# Camera.net
KiCad netlist of a schematic drawn in Altium Designer
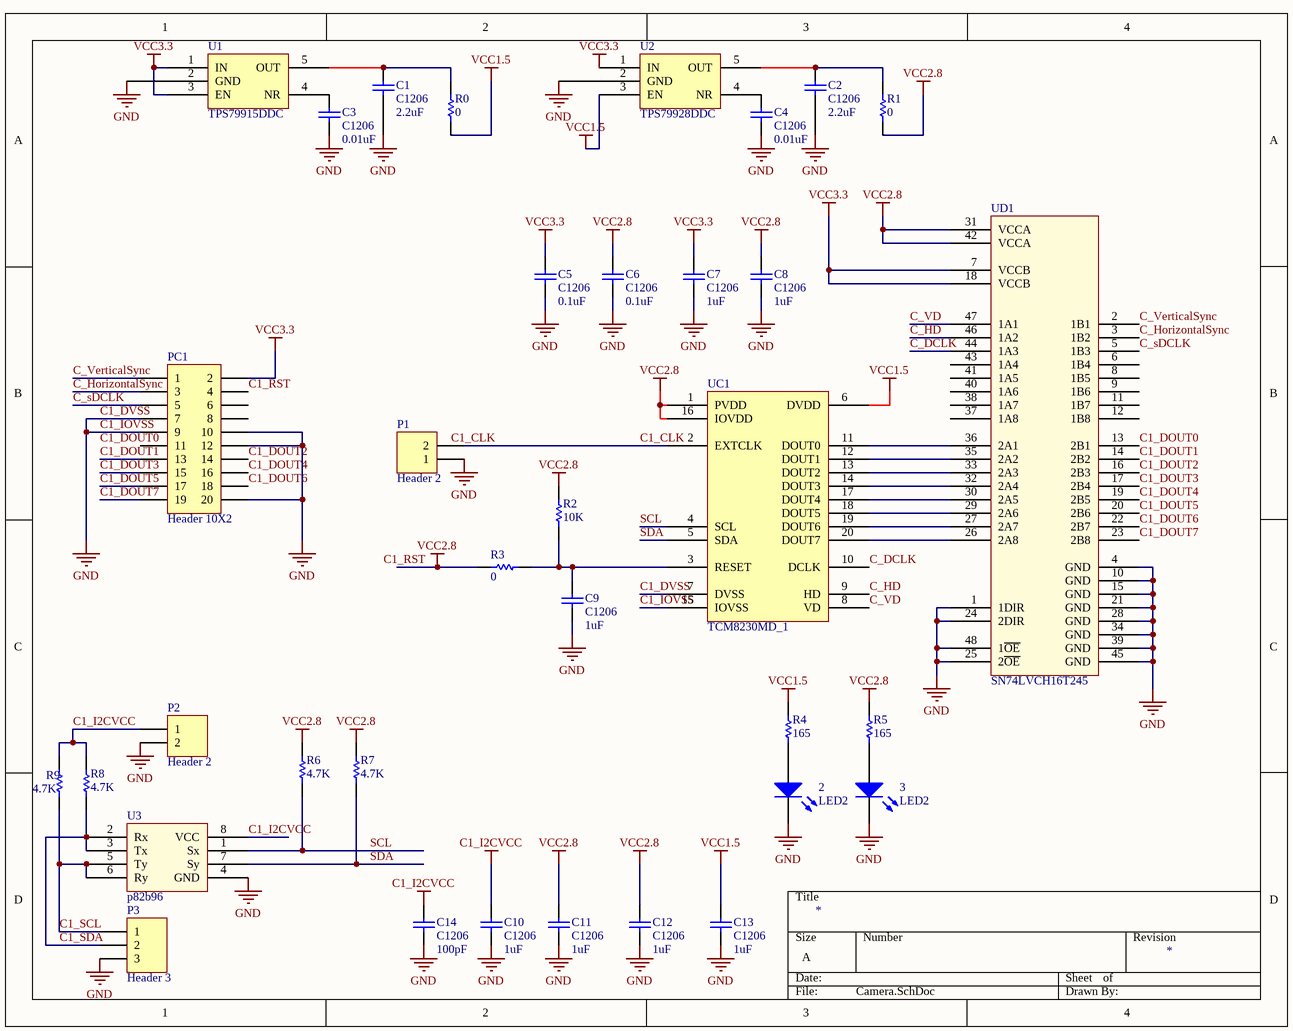
[diagram p0: Camera.SchDoc]

(export (version "E")
  (design (tool "Eeschema 10.0.6"))
  (components
    (comp (ref "2")
      (value "LED2")
      (footprint "DIODE1608")
      (description "Typical RED, GREEN, YELLOW, AMBER GaAs LED")
      (fields (field (name "PUBLISHER") "Altium Limited"))
      (libsource (lib "Miscellaneous Devices") (part "LED2"))
    )
    (comp (ref "3")
      (value "LED2")
      (footprint "DIODE1608")
      (description "Typical RED, GREEN, YELLOW, AMBER GaAs LED")
      (fields (field (name "PUBLISHER") "Altium Limited"))
      (libsource (lib "Miscellaneous Devices") (part "LED2"))
    )
    (comp (ref "C1")
      (value "C1206")
      (footprint "1206")
      (description "Ceramic Chip Capacitor - Standard")
      (fields (field (name "ALTIUM_VALUE") "2.2uF") (field (name "PUBLISHER") "Altium Limited"))
      (libsource (lib "KEMET Chip Capacitor") (part "C1206"))
    )
    (comp (ref "C2")
      (value "C1206")
      (footprint "1206")
      (description "Ceramic Chip Capacitor - Standard")
      (fields (field (name "ALTIUM_VALUE") "2.2uF") (field (name "PUBLISHER") "Altium Limited"))
      (libsource (lib "KEMET Chip Capacitor") (part "C1206"))
    )
    (comp (ref "C3")
      (value "C1206")
      (footprint "1206")
      (description "Ceramic Chip Capacitor - Standard")
      (fields (field (name "ALTIUM_VALUE") "0.01uF") (field (name "PUBLISHER") "Altium Limited"))
      (libsource (lib "KEMET Chip Capacitor") (part "C1206"))
    )
    (comp (ref "C4")
      (value "C1206")
      (footprint "1206")
      (description "Ceramic Chip Capacitor - Standard")
      (fields (field (name "ALTIUM_VALUE") "0.01uF") (field (name "PUBLISHER") "Altium Limited"))
      (libsource (lib "KEMET Chip Capacitor") (part "C1206"))
    )
    (comp (ref "C5")
      (value "C1206")
      (footprint "1206")
      (description "Ceramic Chip Capacitor - Standard")
      (fields (field (name "ALTIUM_VALUE") "0.1uF") (field (name "PUBLISHER") "Altium Limited"))
      (libsource (lib "KEMET Chip Capacitor") (part "C1206"))
    )
    (comp (ref "C6")
      (value "C1206")
      (footprint "1206")
      (description "Ceramic Chip Capacitor - Standard")
      (fields (field (name "ALTIUM_VALUE") "0.1uF") (field (name "PUBLISHER") "Altium Limited"))
      (libsource (lib "KEMET Chip Capacitor") (part "C1206"))
    )
    (comp (ref "C7")
      (value "C1206")
      (footprint "1206")
      (description "Ceramic Chip Capacitor - Standard")
      (fields (field (name "ALTIUM_VALUE") "1uF") (field (name "PUBLISHER") "Altium Limited"))
      (libsource (lib "KEMET Chip Capacitor") (part "C1206"))
    )
    (comp (ref "C8")
      (value "C1206")
      (footprint "1206")
      (description "Ceramic Chip Capacitor - Standard")
      (fields (field (name "ALTIUM_VALUE") "1uF") (field (name "PUBLISHER") "Altium Limited"))
      (libsource (lib "KEMET Chip Capacitor") (part "C1206"))
    )
    (comp (ref "C9")
      (value "C1206")
      (footprint "1206")
      (description "Ceramic Chip Capacitor - Standard")
      (fields (field (name "ALTIUM_VALUE") "1uF") (field (name "PUBLISHER") "Altium Limited"))
      (libsource (lib "KEMET Chip Capacitor") (part "C1206"))
    )
    (comp (ref "C10")
      (value "C1206")
      (footprint "1206")
      (description "Ceramic Chip Capacitor - Standard")
      (fields (field (name "ALTIUM_VALUE") "1uF") (field (name "PUBLISHER") "Altium Limited"))
      (libsource (lib "KEMET Chip Capacitor") (part "C1206"))
    )
    (comp (ref "C11")
      (value "C1206")
      (footprint "1206")
      (description "Ceramic Chip Capacitor - Standard")
      (fields (field (name "ALTIUM_VALUE") "1uF") (field (name "PUBLISHER") "Altium Limited"))
      (libsource (lib "KEMET Chip Capacitor") (part "C1206"))
    )
    (comp (ref "C12")
      (value "C1206")
      (footprint "1206")
      (description "Ceramic Chip Capacitor - Standard")
      (fields (field (name "ALTIUM_VALUE") "1uF") (field (name "PUBLISHER") "Altium Limited"))
      (libsource (lib "KEMET Chip Capacitor") (part "C1206"))
    )
    (comp (ref "C13")
      (value "C1206")
      (footprint "1206")
      (description "Ceramic Chip Capacitor - Standard")
      (fields (field (name "ALTIUM_VALUE") "1uF") (field (name "PUBLISHER") "Altium Limited"))
      (libsource (lib "KEMET Chip Capacitor") (part "C1206"))
    )
    (comp (ref "C14")
      (value "C1206")
      (footprint "1206")
      (description "Ceramic Chip Capacitor - Standard")
      (fields (field (name "ALTIUM_VALUE") "100pF") (field (name "PUBLISHER") "Altium Limited"))
      (libsource (lib "KEMET Chip Capacitor") (part "C1206"))
    )
    (comp (ref "P1")
      (value "Header 2")
      (footprint "HDR1X2")
      (description "Header, 2-Pin")
      (fields (field (name "PUBLISHER") "Altium Limited"))
      (libsource (lib "") (part "Header 2_1"))
    )
    (comp (ref "P2")
      (value "Header 2")
      (footprint "HDR1X2")
      (description "Header, 2-Pin")
      (fields (field (name "PUBLISHER") "Altium Limited"))
      (libsource (lib "Miscellaneous Connectors") (part "Header 2"))
    )
    (comp (ref "P3")
      (value "Header 3")
      (footprint "HDR1X3")
      (description "Header, 3-Pin")
      (fields (field (name "PUBLISHER") "Altium Limited"))
      (libsource (lib "Miscellaneous Connectors") (part "Header 3"))
    )
    (comp (ref "PC1")
      (value "Header 10X2")
      (footprint "HDR2X10")
      (description "Header, 10-Pin, Dual row")
      (fields (field (name "PUBLISHER") "Altium Limited"))
      (libsource (lib "Miscellaneous Connectors") (part "Header 10X2"))
    )
    (comp (ref "R0")
      (value "0")
      (footprint "8-1206")
      (description "Thick Film Chip Resistor, 1 Ohm to 10M Ohm Range, 5% Tolerance, 1206 Size, 0.25 W")
      (fields (field (name "PUBLISHER") "Altium Limited"))
      (libsource (lib "Panasonic Resistor") (part "ERJ8GE"))
    )
    (comp (ref "R1")
      (value "0")
      (footprint "8-1206")
      (description "Thick Film Chip Resistor, 1 Ohm to 10M Ohm Range, 5% Tolerance, 1206 Size, 0.25 W")
      (fields (field (name "PUBLISHER") "Altium Limited"))
      (libsource (lib "Panasonic Resistor") (part "ERJ8GE"))
    )
    (comp (ref "R2")
      (value "10K")
      (footprint "8-1206")
      (description "Thick Film Chip Resistor, 1 Ohm to 10M Ohm Range, 5% Tolerance, 1206 Size, 0.25 W")
      (fields (field (name "PUBLISHER") "Altium Limited"))
      (libsource (lib "Panasonic Resistor") (part "ERJ8GE"))
    )
    (comp (ref "R3")
      (value "0")
      (footprint "8-1206")
      (description "Thick Film Chip Resistor, 1 Ohm to 10M Ohm Range, 5% Tolerance, 1206 Size, 0.25 W")
      (fields (field (name "PUBLISHER") "Altium Limited"))
      (libsource (lib "Panasonic Resistor") (part "ERJ8GE"))
    )
    (comp (ref "R4")
      (value "165")
      (footprint "8-1206")
      (description "Thick Film Chip Resistor, 1 Ohm to 10M Ohm Range, 5% Tolerance, 1206 Size, 0.25 W")
      (fields (field (name "PUBLISHER") "Altium Limited"))
      (libsource (lib "Panasonic Resistor") (part "ERJ8GE"))
    )
    (comp (ref "R5")
      (value "165")
      (footprint "8-1206")
      (description "Thick Film Chip Resistor, 1 Ohm to 10M Ohm Range, 5% Tolerance, 1206 Size, 0.25 W")
      (fields (field (name "PUBLISHER") "Altium Limited"))
      (libsource (lib "Panasonic Resistor") (part "ERJ8GE"))
    )
    (comp (ref "R6")
      (value "4.7K")
      (footprint "8-1206")
      (description "Thick Film Chip Resistor, 1 Ohm to 10M Ohm Range, 5% Tolerance, 1206 Size, 0.25 W")
      (fields (field (name "PUBLISHER") "Altium Limited"))
      (libsource (lib "Panasonic Resistor") (part "ERJ8GE"))
    )
    (comp (ref "R7")
      (value "4.7K")
      (footprint "8-1206")
      (description "Thick Film Chip Resistor, 1 Ohm to 10M Ohm Range, 5% Tolerance, 1206 Size, 0.25 W")
      (fields (field (name "PUBLISHER") "Altium Limited"))
      (libsource (lib "Panasonic Resistor") (part "ERJ8GE"))
    )
    (comp (ref "R8")
      (value "4.7K")
      (footprint "8-1206")
      (description "Thick Film Chip Resistor, 1 Ohm to 10M Ohm Range, 5% Tolerance, 1206 Size, 0.25 W")
      (fields (field (name "PUBLISHER") "Altium Limited"))
      (libsource (lib "Panasonic Resistor") (part "ERJ8GE"))
    )
    (comp (ref "R9")
      (value "4.7K")
      (footprint "8-1206")
      (description "Thick Film Chip Resistor, 1 Ohm to 10M Ohm Range, 5% Tolerance, 1206 Size, 0.25 W")
      (fields (field (name "PUBLISHER") "Altium Limited"))
      (libsource (lib "Panasonic Resistor") (part "ERJ8GE"))
    )
    (comp (ref "U1")
      (value "TPS79915DDC")
      (footprint "TSOT23-5")
      (description "200mA, Low Quiescent Current, Ultra-Low Noise, High PSRR  Low Dropout Linear Regulator")
      (libsource (lib "Capstone_Lib") (part "TPS799xxDDC"))
    )
    (comp (ref "U2")
      (value "TPS79928DDC")
      (footprint "TSOT23-5")
      (description "200mA, Low Quiescent Current, Ultra-Low Noise, High PSRR  Low Dropout Linear Regulator")
      (libsource (lib "Capstone_Lib") (part "TPS799xxDDC"))
    )
    (comp (ref "U3") (value "p82b96") (footprint "DIP-8") (libsource (lib "p82b96") (part "p82b96")))
    (comp (ref "UC1")
      (value "TCM8230MD_1")
      (footprint "TCM8230MD")
      (description "VGA CAMERA MODULE 640x480")
      (libsource (lib "daughterboard") (part "TCM8230MD_1"))
    )
    (comp (ref "UD1")
      (value "SN74LVCH16T245")
      (footprint "SN74LVCH16T245")
      (description "16-bit bus transceiver with voltage regulation.")
      (libsource (lib "daughterboard") (part "SN74LVCH16T245"))
    )
  )
  (nets
    (net (code "1") (name "/C1_CLK") (class "Default")
      (node (ref "P1") (pin "2") (pinfunction "2_2") (pintype "passive"))
      (node (ref "UC1") (pin "2") (pinfunction "EXTCLK_2") (pintype "passive"))
    )
    (net (code "2") (name "/C1_DOUT0") (class "Default")
      (node (ref "UD1") (pin "13") (pinfunction "2B1_13") (pintype "passive"))
    )
    (net (code "3") (name "/C1_DOUT1") (class "Default")
      (node (ref "PC1") (pin "13") (pinfunction "13_13") (pintype "passive"))
      (node (ref "UD1") (pin "14") (pinfunction "2B2_14") (pintype "passive"))
    )
    (net (code "4") (name "/C1_DOUT2") (class "Default")
      (node (ref "PC1") (pin "14") (pinfunction "14_14") (pintype "passive"))
      (node (ref "UD1") (pin "16") (pinfunction "2B3_16") (pintype "passive"))
    )
    (net (code "5") (name "/C1_DOUT3") (class "Default")
      (node (ref "PC1") (pin "15") (pinfunction "15_15") (pintype "passive"))
      (node (ref "UD1") (pin "17") (pinfunction "2B4_17") (pintype "passive"))
    )
    (net (code "6") (name "/C1_DOUT4") (class "Default")
      (node (ref "PC1") (pin "16") (pinfunction "16_16") (pintype "passive"))
      (node (ref "UD1") (pin "19") (pinfunction "2B5_19") (pintype "passive"))
    )
    (net (code "7") (name "/C1_DOUT5") (class "Default")
      (node (ref "PC1") (pin "17") (pinfunction "17_17") (pintype "passive"))
      (node (ref "UD1") (pin "20") (pinfunction "2B6_20") (pintype "passive"))
    )
    (net (code "8") (name "/C1_DOUT6") (class "Default")
      (node (ref "PC1") (pin "18") (pinfunction "18_18") (pintype "passive"))
      (node (ref "UD1") (pin "22") (pinfunction "2B7_22") (pintype "passive"))
    )
    (net (code "9") (name "/C1_DOUT7") (class "Default")
      (node (ref "PC1") (pin "19") (pinfunction "19_19") (pintype "passive"))
      (node (ref "UD1") (pin "23") (pinfunction "2B8_23") (pintype "passive"))
    )
    (net (code "10") (name "/C1_RST") (class "Default")
      (node (ref "PC1") (pin "4") (pinfunction "4_4") (pintype "passive"))
    )
    (net (code "11") (name "/C1_SCL") (class "Default")
      (node (ref "P3") (pin "1") (pinfunction "1_1") (pintype "passive"))
      (node (ref "R9") (pin "1") (pinfunction "1_1") (pintype "passive"))
      (node (ref "U3") (pin "5") (pinfunction "Ty_5") (pintype "passive"))
      (node (ref "U3") (pin "6") (pinfunction "Ry_6") (pintype "passive"))
    )
    (net (code "12") (name "/C1_SDA") (class "Default")
      (node (ref "P3") (pin "2") (pinfunction "2_2") (pintype "passive"))
      (node (ref "R8") (pin "1") (pinfunction "1_1") (pintype "passive"))
      (node (ref "U3") (pin "2") (pinfunction "Rx_2") (pintype "passive"))
      (node (ref "U3") (pin "3") (pinfunction "Tx_3") (pintype "passive"))
    )
    (net (code "13") (name "/C_DCLK") (class "Default")
      (node (ref "UC1") (pin "10") (pinfunction "DCLK_10") (pintype "passive"))
      (node (ref "UD1") (pin "44") (pinfunction "1A3_44") (pintype "passive"))
    )
    (net (code "14") (name "/C_HD") (class "Default")
      (node (ref "UC1") (pin "9") (pinfunction "HD_9") (pintype "passive"))
      (node (ref "UD1") (pin "46") (pinfunction "1A2_46") (pintype "passive"))
    )
    (net (code "15") (name "/C_HorizontalSync") (class "Default")
      (node (ref "PC1") (pin "3") (pinfunction "3_3") (pintype "passive"))
      (node (ref "UD1") (pin "3") (pinfunction "1B2_3") (pintype "passive"))
    )
    (net (code "16") (name "/C_VD") (class "Default")
      (node (ref "UC1") (pin "8") (pinfunction "VD_8") (pintype "passive"))
      (node (ref "UD1") (pin "47") (pinfunction "1A1_47") (pintype "passive"))
    )
    (net (code "17") (name "/C_VerticalSync") (class "Default")
      (node (ref "PC1") (pin "1") (pinfunction "1_1") (pintype "passive"))
      (node (ref "UD1") (pin "2") (pinfunction "1B1_2") (pintype "passive"))
    )
    (net (code "18") (name "/C_sDCLK") (class "Default")
      (node (ref "PC1") (pin "5") (pinfunction "5_5") (pintype "passive"))
      (node (ref "UD1") (pin "5") (pinfunction "1B3_5") (pintype "passive"))
    )
    (net (code "19") (name "/SCL") (class "Default")
      (node (ref "R6") (pin "1") (pinfunction "1_1") (pintype "passive"))
      (node (ref "U3") (pin "1") (pinfunction "Sx_1") (pintype "passive"))
      (node (ref "UC1") (pin "4") (pinfunction "SCL_4") (pintype "passive"))
    )
    (net (code "20") (name "/SDA") (class "Default")
      (node (ref "R7") (pin "1") (pinfunction "1_1") (pintype "passive"))
      (node (ref "U3") (pin "7") (pinfunction "Sy_7") (pintype "passive"))
      (node (ref "UC1") (pin "5") (pinfunction "SDA_5") (pintype "passive"))
    )
    (net (code "21") (name "C1_I2CVCC") (class "Default")
      (node (ref "C10") (pin "2") (pinfunction "2_2") (pintype "passive"))
      (node (ref "C14") (pin "2") (pinfunction "2_2") (pintype "passive"))
      (node (ref "P2") (pin "1") (pinfunction "1_1") (pintype "passive"))
      (node (ref "R8") (pin "2") (pinfunction "2_2") (pintype "passive"))
      (node (ref "R9") (pin "2") (pinfunction "2_2") (pintype "passive"))
      (node (ref "U3") (pin "8") (pinfunction "VCC_8") (pintype "passive"))
    )
    (net (code "22") (name "GND") (class "Default")
      (node (ref "2") (pin "2") (pinfunction "K_2") (pintype "passive"))
      (node (ref "3") (pin "2") (pinfunction "K_2") (pintype "passive"))
      (node (ref "C1") (pin "1") (pinfunction "1_1") (pintype "passive"))
      (node (ref "C10") (pin "1") (pinfunction "1_1") (pintype "passive"))
      (node (ref "C11") (pin "1") (pinfunction "1_1") (pintype "passive"))
      (node (ref "C12") (pin "1") (pinfunction "1_1") (pintype "passive"))
      (node (ref "C13") (pin "1") (pinfunction "1_1") (pintype "passive"))
      (node (ref "C14") (pin "1") (pinfunction "1_1") (pintype "passive"))
      (node (ref "C2") (pin "1") (pinfunction "1_1") (pintype "passive"))
      (node (ref "C3") (pin "1") (pinfunction "1_1") (pintype "passive"))
      (node (ref "C4") (pin "1") (pinfunction "1_1") (pintype "passive"))
      (node (ref "C5") (pin "1") (pinfunction "1_1") (pintype "passive"))
      (node (ref "C6") (pin "1") (pinfunction "1_1") (pintype "passive"))
      (node (ref "C7") (pin "1") (pinfunction "1_1") (pintype "passive"))
      (node (ref "C8") (pin "1") (pinfunction "1_1") (pintype "passive"))
      (node (ref "C9") (pin "1") (pinfunction "1_1") (pintype "passive"))
      (node (ref "P1") (pin "1") (pinfunction "1_1") (pintype "passive"))
      (node (ref "P2") (pin "2") (pinfunction "2_2") (pintype "passive"))
      (node (ref "P3") (pin "3") (pinfunction "3_3") (pintype "passive"))
      (node (ref "PC1") (pin "10") (pinfunction "10_10") (pintype "passive"))
      (node (ref "PC1") (pin "12") (pinfunction "12_12") (pintype "passive"))
      (node (ref "PC1") (pin "20") (pinfunction "20_20") (pintype "passive"))
      (node (ref "PC1") (pin "7") (pinfunction "7_7") (pintype "passive"))
      (node (ref "PC1") (pin "9") (pinfunction "9_9") (pintype "passive"))
      (node (ref "U1") (pin "2") (pinfunction "GND_2") (pintype "passive"))
      (node (ref "U2") (pin "2") (pinfunction "GND_2") (pintype "passive"))
      (node (ref "U3") (pin "4") (pinfunction "GND_4") (pintype "passive"))
      (node (ref "UC1") (pin "15") (pinfunction "IOVSS_15") (pintype "passive"))
      (node (ref "UC1") (pin "7") (pinfunction "DVSS_7") (pintype "passive"))
      (node (ref "UD1") (pin "1") (pinfunction "1DIR_1") (pintype "passive"))
      (node (ref "UD1") (pin "10") (pinfunction "GND_10") (pintype "passive"))
      (node (ref "UD1") (pin "15") (pinfunction "GND_15") (pintype "passive"))
      (node (ref "UD1") (pin "21") (pinfunction "GND_21") (pintype "passive"))
      (node (ref "UD1") (pin "24") (pinfunction "2DIR_24") (pintype "passive"))
      (node (ref "UD1") (pin "25") (pinfunction "2~{OE}_25") (pintype "passive"))
      (node (ref "UD1") (pin "28") (pinfunction "GND_28") (pintype "passive"))
      (node (ref "UD1") (pin "34") (pinfunction "GND_34") (pintype "passive"))
      (node (ref "UD1") (pin "39") (pinfunction "GND_39") (pintype "passive"))
      (node (ref "UD1") (pin "4") (pinfunction "GND_4") (pintype "passive"))
      (node (ref "UD1") (pin "45") (pinfunction "GND_45") (pintype "passive"))
      (node (ref "UD1") (pin "48") (pinfunction "1~{OE}_48") (pintype "passive"))
    )
    (net (code "23") (name "Net-(2-A)") (class "Default")
      (node (ref "2") (pin "1") (pinfunction "A_1") (pintype "passive"))
      (node (ref "R4") (pin "1") (pinfunction "1_1") (pintype "passive"))
    )
    (net (code "24") (name "Net-(3-A)") (class "Default")
      (node (ref "3") (pin "1") (pinfunction "A_1") (pintype "passive"))
      (node (ref "R5") (pin "1") (pinfunction "1_1") (pintype "passive"))
    )
    (net (code "25") (name "Net-(U1-NR)") (class "Default")
      (node (ref "C3") (pin "2") (pinfunction "2_2") (pintype "passive"))
      (node (ref "U1") (pin "4") (pinfunction "NR_4") (pintype "passive"))
    )
    (net (code "26") (name "Net-(U1-OUT)") (class "Default")
      (node (ref "C1") (pin "2") (pinfunction "2_2") (pintype "passive"))
      (node (ref "R0") (pin "2") (pinfunction "2_2") (pintype "passive"))
      (node (ref "U1") (pin "5") (pinfunction "OUT_5") (pintype "passive"))
    )
    (net (code "27") (name "Net-(U2-NR)") (class "Default")
      (node (ref "C4") (pin "2") (pinfunction "2_2") (pintype "passive"))
      (node (ref "U2") (pin "4") (pinfunction "NR_4") (pintype "passive"))
    )
    (net (code "28") (name "Net-(U2-OUT)") (class "Default")
      (node (ref "C2") (pin "2") (pinfunction "2_2") (pintype "passive"))
      (node (ref "R1") (pin "2") (pinfunction "2_2") (pintype "passive"))
      (node (ref "U2") (pin "5") (pinfunction "OUT_5") (pintype "passive"))
    )
    (net (code "29") (name "Net-(UC1-DOUT0)") (class "Default")
      (node (ref "UC1") (pin "11") (pinfunction "DOUT0_11") (pintype "passive"))
      (node (ref "UD1") (pin "36") (pinfunction "2A1_36") (pintype "passive"))
    )
    (net (code "30") (name "Net-(UC1-DOUT1)") (class "Default")
      (node (ref "UC1") (pin "12") (pinfunction "DOUT1_12") (pintype "passive"))
      (node (ref "UD1") (pin "35") (pinfunction "2A2_35") (pintype "passive"))
    )
    (net (code "31") (name "Net-(UC1-DOUT2)") (class "Default")
      (node (ref "UC1") (pin "13") (pinfunction "DOUT2_13") (pintype "passive"))
      (node (ref "UD1") (pin "33") (pinfunction "2A3_33") (pintype "passive"))
    )
    (net (code "32") (name "Net-(UC1-DOUT3)") (class "Default")
      (node (ref "UC1") (pin "14") (pinfunction "DOUT3_14") (pintype "passive"))
      (node (ref "UD1") (pin "32") (pinfunction "2A4_32") (pintype "passive"))
    )
    (net (code "33") (name "Net-(UC1-DOUT4)") (class "Default")
      (node (ref "UC1") (pin "17") (pinfunction "DOUT4_17") (pintype "passive"))
      (node (ref "UD1") (pin "30") (pinfunction "2A5_30") (pintype "passive"))
    )
    (net (code "34") (name "Net-(UC1-DOUT5)") (class "Default")
      (node (ref "UC1") (pin "18") (pinfunction "DOUT5_18") (pintype "passive"))
      (node (ref "UD1") (pin "29") (pinfunction "2A6_29") (pintype "passive"))
    )
    (net (code "35") (name "Net-(UC1-DOUT6)") (class "Default")
      (node (ref "UC1") (pin "19") (pinfunction "DOUT6_19") (pintype "passive"))
      (node (ref "UD1") (pin "27") (pinfunction "2A7_27") (pintype "passive"))
    )
    (net (code "36") (name "Net-(UC1-DOUT7)") (class "Default")
      (node (ref "UC1") (pin "20") (pinfunction "DOUT7_20") (pintype "passive"))
      (node (ref "UD1") (pin "26") (pinfunction "2A8_26") (pintype "passive"))
    )
    (net (code "37") (name "Net-(UC1-RESET)") (class "Default")
      (node (ref "C9") (pin "2") (pinfunction "2_2") (pintype "passive"))
      (node (ref "R2") (pin "1") (pinfunction "1_1") (pintype "passive"))
      (node (ref "R3") (pin "2") (pinfunction "2_2") (pintype "passive"))
      (node (ref "UC1") (pin "3") (pinfunction "RESET_3") (pintype "passive"))
    )
    (net (code "38") (name "VCC1.5") (class "Default")
      (node (ref "C13") (pin "2") (pinfunction "2_2") (pintype "passive"))
      (node (ref "R0") (pin "1") (pinfunction "1_1") (pintype "passive"))
      (node (ref "R4") (pin "2") (pinfunction "2_2") (pintype "passive"))
      (node (ref "U2") (pin "3") (pinfunction "EN_3") (pintype "passive"))
      (node (ref "UC1") (pin "6") (pinfunction "DVDD_6") (pintype "passive"))
    )
    (net (code "39") (name "VCC2.8") (class "Default")
      (node (ref "C11") (pin "2") (pinfunction "2_2") (pintype "passive"))
      (node (ref "C12") (pin "2") (pinfunction "2_2") (pintype "passive"))
      (node (ref "C6") (pin "2") (pinfunction "2_2") (pintype "passive"))
      (node (ref "C8") (pin "2") (pinfunction "2_2") (pintype "passive"))
      (node (ref "R1") (pin "1") (pinfunction "1_1") (pintype "passive"))
      (node (ref "R2") (pin "2") (pinfunction "2_2") (pintype "passive"))
      (node (ref "R3") (pin "1") (pinfunction "1_1") (pintype "passive"))
      (node (ref "R5") (pin "2") (pinfunction "2_2") (pintype "passive"))
      (node (ref "R6") (pin "2") (pinfunction "2_2") (pintype "passive"))
      (node (ref "R7") (pin "2") (pinfunction "2_2") (pintype "passive"))
      (node (ref "UC1") (pin "1") (pinfunction "PVDD_1") (pintype "passive"))
      (node (ref "UC1") (pin "16") (pinfunction "IOVDD_16") (pintype "passive"))
      (node (ref "UD1") (pin "31") (pinfunction "VCCA_31") (pintype "passive"))
      (node (ref "UD1") (pin "42") (pinfunction "VCCA_42") (pintype "passive"))
    )
    (net (code "40") (name "VCC3.3") (class "Default")
      (node (ref "C5") (pin "2") (pinfunction "2_2") (pintype "passive"))
      (node (ref "C7") (pin "2") (pinfunction "2_2") (pintype "passive"))
      (node (ref "PC1") (pin "2") (pinfunction "2_2") (pintype "passive"))
      (node (ref "U1") (pin "1") (pinfunction "IN_1") (pintype "passive"))
      (node (ref "U1") (pin "3") (pinfunction "EN_3") (pintype "passive"))
      (node (ref "U2") (pin "1") (pinfunction "IN_1") (pintype "passive"))
      (node (ref "UD1") (pin "18") (pinfunction "VCCB_18") (pintype "passive"))
      (node (ref "UD1") (pin "7") (pinfunction "VCCB_7") (pintype "passive"))
    )
    (net (code "41") (name "unconnected-(PC1-Pad6)") (class "Default")
      (node (ref "PC1") (pin "6") (pinfunction "6_6") (pintype "passive"))
    )
    (net (code "42") (name "unconnected-(PC1-Pad8)") (class "Default")
      (node (ref "PC1") (pin "8") (pinfunction "8_8") (pintype "passive"))
    )
    (net (code "43") (name "unconnected-(PC1-Pad11)") (class "Default")
      (node (ref "PC1") (pin "11") (pinfunction "11_11") (pintype "passive"))
    )
    (net (code "44") (name "unconnected-(UD1-1A4-Pad43)") (class "Default")
      (node (ref "UD1") (pin "43") (pinfunction "1A4_43") (pintype "passive"))
    )
    (net (code "45") (name "unconnected-(UD1-1A5-Pad41)") (class "Default")
      (node (ref "UD1") (pin "41") (pinfunction "1A5_41") (pintype "passive"))
    )
    (net (code "46") (name "unconnected-(UD1-1A6-Pad40)") (class "Default")
      (node (ref "UD1") (pin "40") (pinfunction "1A6_40") (pintype "passive"))
    )
    (net (code "47") (name "unconnected-(UD1-1A7-Pad38)") (class "Default")
      (node (ref "UD1") (pin "38") (pinfunction "1A7_38") (pintype "passive"))
    )
    (net (code "48") (name "unconnected-(UD1-1A8-Pad37)") (class "Default")
      (node (ref "UD1") (pin "37") (pinfunction "1A8_37") (pintype "passive"))
    )
    (net (code "49") (name "unconnected-(UD1-1B4-Pad6)") (class "Default")
      (node (ref "UD1") (pin "6") (pinfunction "1B4_6") (pintype "passive"))
    )
    (net (code "50") (name "unconnected-(UD1-1B5-Pad8)") (class "Default")
      (node (ref "UD1") (pin "8") (pinfunction "1B5_8") (pintype "passive"))
    )
    (net (code "51") (name "unconnected-(UD1-1B6-Pad9)") (class "Default")
      (node (ref "UD1") (pin "9") (pinfunction "1B6_9") (pintype "passive"))
    )
    (net (code "52") (name "unconnected-(UD1-1B7-Pad11)") (class "Default")
      (node (ref "UD1") (pin "11") (pinfunction "1B7_11") (pintype "passive"))
    )
    (net (code "53") (name "unconnected-(UD1-1B8-Pad12)") (class "Default")
      (node (ref "UD1") (pin "12") (pinfunction "1B8_12") (pintype "passive"))
    )
  )
)
